# mod_temperature.net
KiCad netlist of a schematic drawn in EAGLE
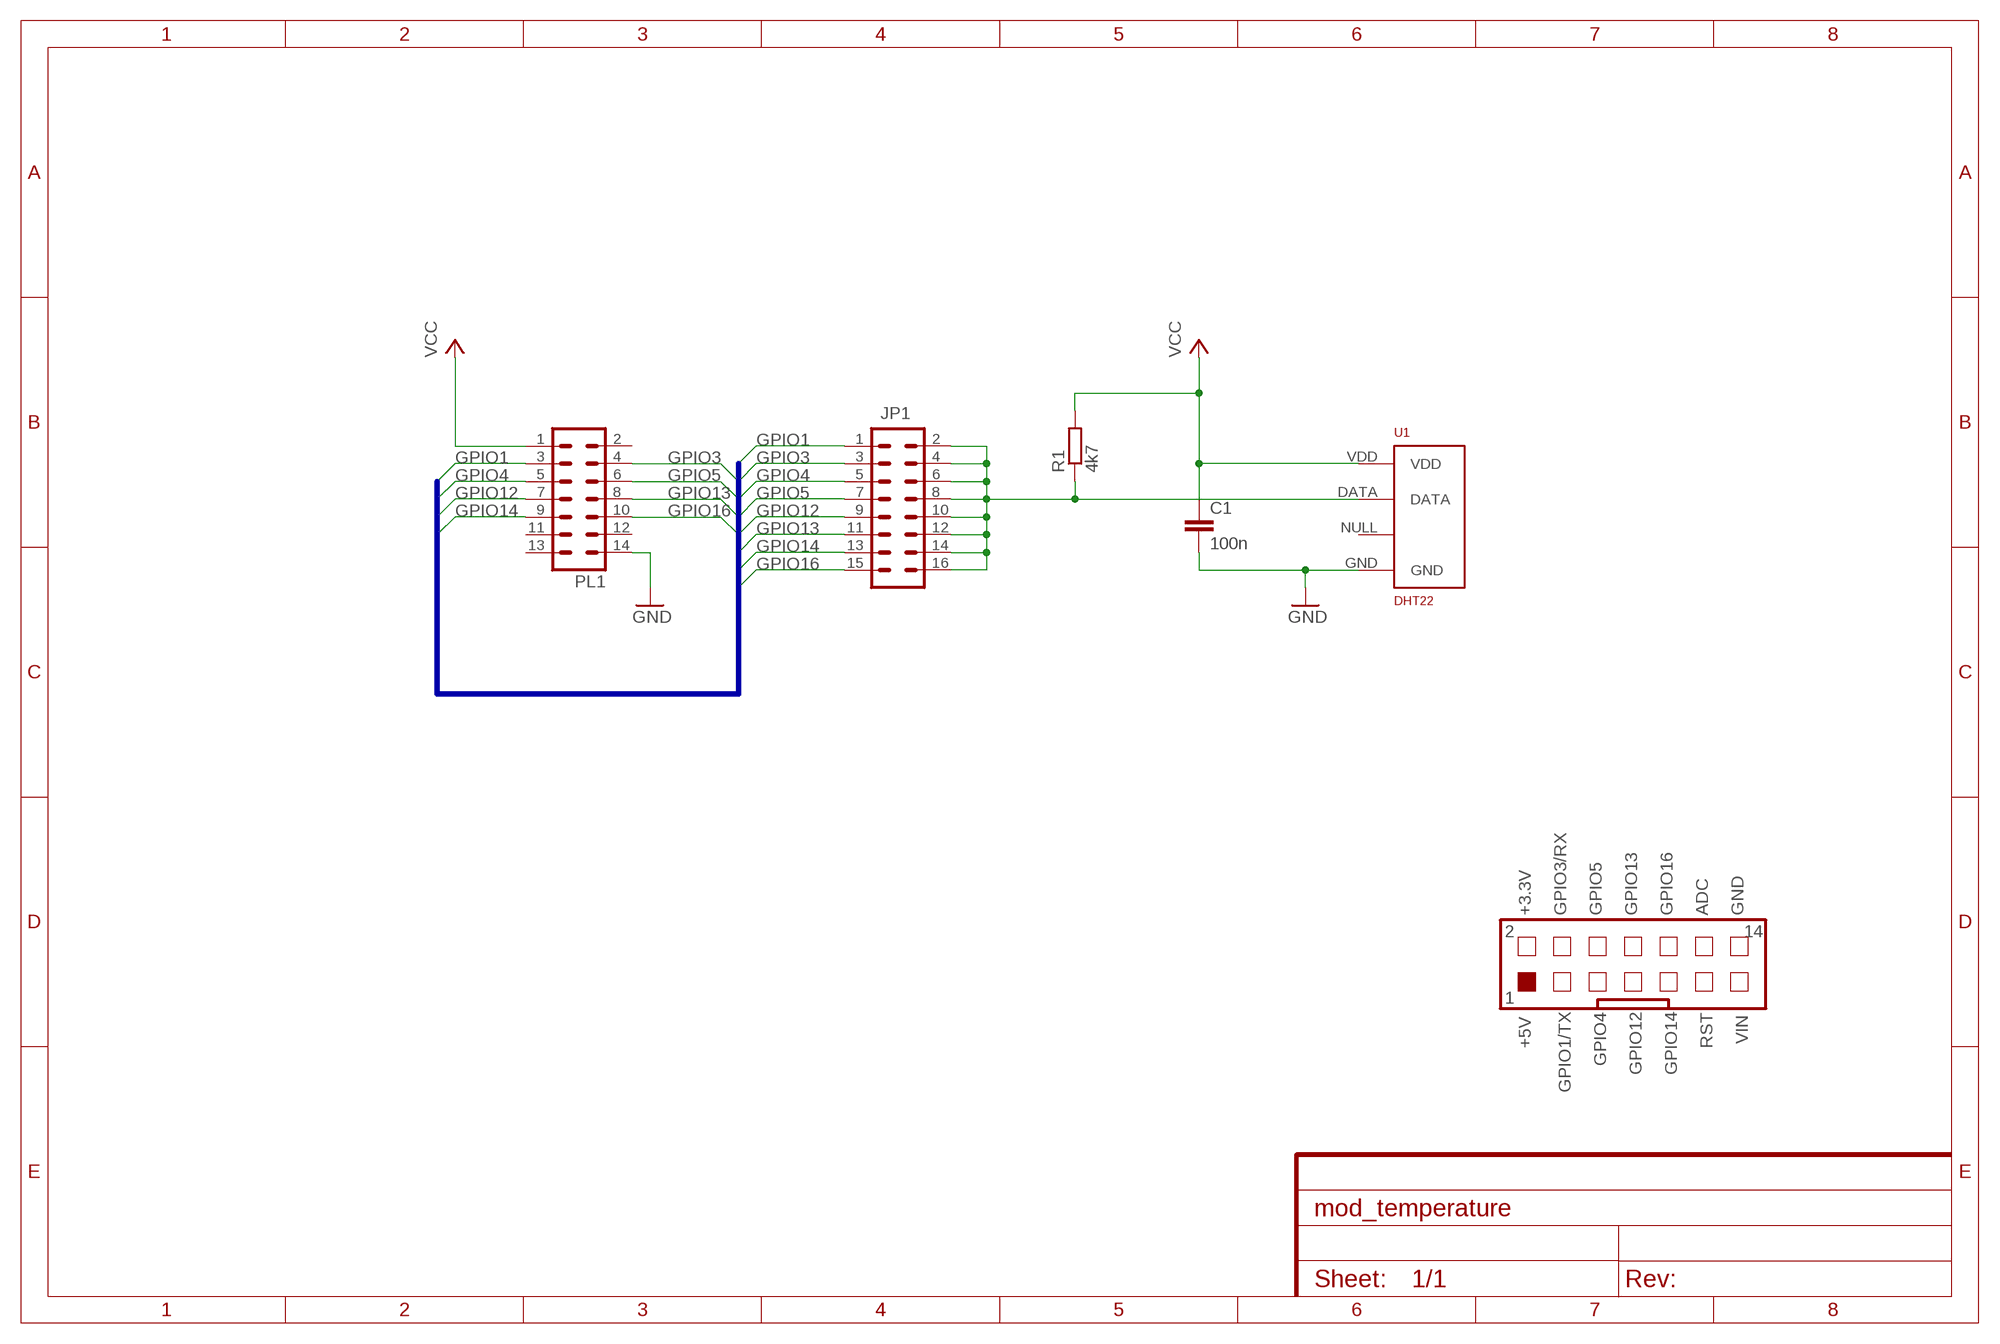
[diagram p0: schematic, sheet 1]

(export (version "E")
  (design (tool "Eeschema 10.0.6"))
  (components
    (comp (ref "C1")
      (value "100n")
      (footprint "eagle-import:C025-025X050")
      (libsource (lib "eagle-import") (part "C-EU025-025X050"))
    )
    (comp (ref "JP1")
      (value "M08X2")
      (footprint "eagle-import:2X8")
      (libsource (lib "eagle-import") (part "M08X2"))
    )
    (comp (ref "PL1")
      (value "14V")
      (footprint "eagle-import:14V")
      (libsource (lib "eagle-import") (part "14V"))
    )
    (comp (ref "R1")
      (value "4k7")
      (footprint "eagle-import:0207_10")
      (libsource (lib "eagle-import") (part "R-EU_0207/10"))
    )
    (comp (ref "U1")
      (value "DHT22")
      (footprint "eagle-import:RHT03_DHT-22_RA")
      (libsource (lib "eagle-import") (part "RHT03_DHT-22_AM2302RA"))
    )
  )
  (nets
    (net (code "1") (name "/GPIO1") (class "Default")
      (node (ref "JP1") (pin "1") (pinfunction "1_1") (pintype "passive"))
      (node (ref "PL1") (pin "3") (pinfunction "3_3") (pintype "passive"))
    )
    (net (code "2") (name "/GPIO3") (class "Default")
      (node (ref "JP1") (pin "3") (pinfunction "3_3") (pintype "passive"))
      (node (ref "PL1") (pin "4") (pinfunction "4_4") (pintype "passive"))
    )
    (net (code "3") (name "/GPIO4") (class "Default")
      (node (ref "JP1") (pin "5") (pinfunction "5_5") (pintype "passive"))
      (node (ref "PL1") (pin "5") (pinfunction "5_5") (pintype "passive"))
    )
    (net (code "4") (name "/GPIO5") (class "Default")
      (node (ref "JP1") (pin "7") (pinfunction "7_7") (pintype "passive"))
      (node (ref "PL1") (pin "6") (pinfunction "6_6") (pintype "passive"))
    )
    (net (code "5") (name "/GPIO12") (class "Default")
      (node (ref "JP1") (pin "9") (pinfunction "9_9") (pintype "passive"))
      (node (ref "PL1") (pin "7") (pinfunction "7_7") (pintype "passive"))
    )
    (net (code "6") (name "/GPIO13") (class "Default")
      (node (ref "JP1") (pin "11") (pinfunction "11_11") (pintype "passive"))
      (node (ref "PL1") (pin "8") (pinfunction "8_8") (pintype "passive"))
    )
    (net (code "7") (name "/GPIO14") (class "Default")
      (node (ref "JP1") (pin "13") (pinfunction "13_13") (pintype "passive"))
      (node (ref "PL1") (pin "9") (pinfunction "9_9") (pintype "passive"))
    )
    (net (code "8") (name "/GPIO16") (class "Default")
      (node (ref "JP1") (pin "15") (pinfunction "15_15") (pintype "passive"))
      (node (ref "PL1") (pin "10") (pinfunction "10_10") (pintype "passive"))
    )
    (net (code "9") (name "GND") (class "Default")
      (node (ref "C1") (pin "2") (pinfunction "2_2") (pintype "passive"))
      (node (ref "PL1") (pin "14") (pinfunction "14_14") (pintype "passive"))
      (node (ref "U1") (pin "GND") (pinfunction "GND_GND") (pintype "power_in"))
    )
    (net (code "10") (name "Net-(JP1-Pad10)") (class "Default")
      (node (ref "JP1") (pin "10") (pinfunction "10_10") (pintype "passive"))
      (node (ref "JP1") (pin "12") (pinfunction "12_12") (pintype "passive"))
      (node (ref "JP1") (pin "14") (pinfunction "14_14") (pintype "passive"))
      (node (ref "JP1") (pin "16") (pinfunction "16_16") (pintype "passive"))
      (node (ref "JP1") (pin "2") (pinfunction "2_2") (pintype "passive"))
      (node (ref "JP1") (pin "4") (pinfunction "4_4") (pintype "passive"))
      (node (ref "JP1") (pin "6") (pinfunction "6_6") (pintype "passive"))
      (node (ref "JP1") (pin "8") (pinfunction "8_8") (pintype "passive"))
      (node (ref "R1") (pin "1") (pinfunction "1_1") (pintype "passive"))
      (node (ref "U1") (pin "DATA") (pinfunction "DATA_DATA") (pintype "bidirectional"))
    )
    (net (code "11") (name "VCC") (class "Default")
      (node (ref "C1") (pin "1") (pinfunction "1_1") (pintype "passive"))
      (node (ref "PL1") (pin "1") (pinfunction "1_1") (pintype "passive"))
      (node (ref "R1") (pin "2") (pinfunction "2_2") (pintype "passive"))
      (node (ref "U1") (pin "VDD") (pinfunction "VDD_VDD") (pintype "power_in"))
    )
    (net (code "12") (name "unconnected-(PL1-Pad2)") (class "Default")
      (node (ref "PL1") (pin "2") (pinfunction "2_2") (pintype "passive"))
    )
    (net (code "13") (name "unconnected-(PL1-Pad11)") (class "Default")
      (node (ref "PL1") (pin "11") (pinfunction "11_11") (pintype "passive"))
    )
    (net (code "14") (name "unconnected-(PL1-Pad12)") (class "Default")
      (node (ref "PL1") (pin "12") (pinfunction "12_12") (pintype "passive"))
    )
    (net (code "15") (name "unconnected-(PL1-Pad13)") (class "Default")
      (node (ref "PL1") (pin "13") (pinfunction "13_13") (pintype "passive"))
    )
    (net (code "16") (name "unconnected-(U1-PadNULL)") (class "Default")
      (node (ref "U1") (pin "NULL") (pinfunction "NULL_NULL") (pintype "no_connect"))
    )
  )
)
